# Solar_Battery_Charger.net
KiCad netlist of a schematic drawn in Altium Designer
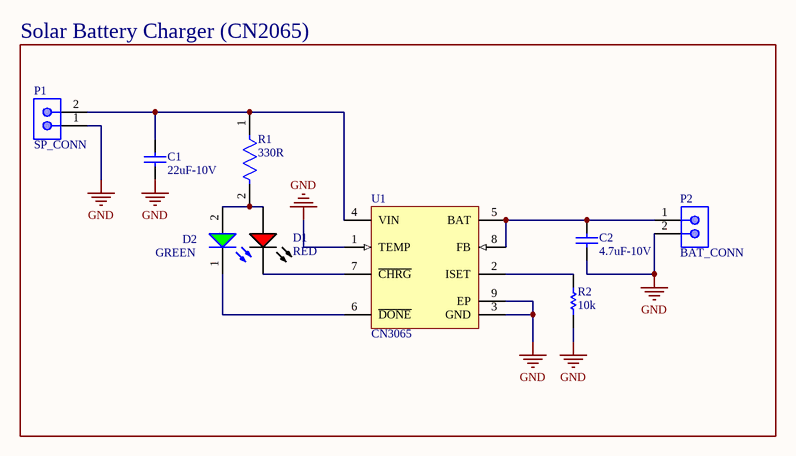
[diagram p0: Solar Battery Charger.SchDoc]

(export (version "E")
  (design (tool "Eeschema 10.0.6"))
  (components
    (comp (ref "C1")
      (value "22uF-10V")
      (footprint "CAPC2013X95X45ML15T25")
      (fields (field (name "MANUFACTURER") "Murata") (field (name "PART NUMBER") "GRM219R61A226MEA0D"))
      (libsource (lib "Altium Content Vault") (part "CAP"))
    )
    (comp (ref "C2")
      (value "4.7uF-10V")
      (footprint "CAPC2013X95X45LL10T25")
      (fields (field (name "MANUFACTURER") "Murata") (field (name "PART NUMBER") "GRM219R61A475KE34J"))
      (libsource (lib "Altium Content Vault") (part "CAP"))
    )
    (comp (ref "D1")
      (value "RED")
      (footprint "AVAG-HSMX-C190_V")
      (description "LED Uni-Color Red, 65 mW, 20 mA, -40 to 85 degC, 2-Pin SMD, RoHS, Tape and Reel")
      (libsource (lib "Altium Content Vault") (part "LED-RED-AK-2"))
    )
    (comp (ref "D2")
      (value "GREEN")
      (footprint "WL-SMCW_0603_150060xx75000")
      (description "WURTH ELEKTRONIK - 150060VS75000 - LED, Green, SMD, 0603, 30 mA, 2 V, 570 nm")
      (libsource (lib "Altium Content Vault") (part "LED_Green_2A-1K"))
    )
    (comp (ref "P1")
      (value "SP_CONN")
      (footprint "MOLX-22-23-2021_V")
      (fields (field (name "PARTNUMBER") "22-23-2021"))
      (libsource (lib "Altium Content Vault") (part "CN-1P-M-R2"))
    )
    (comp (ref "P2")
      (value "BAT_CONN")
      (footprint "MOLX-22-23-2021_V")
      (fields (field (name "PARTNUMBER") "22-23-2021"))
      (libsource (lib "") (part "CN-1P-M-R2_1"))
    )
    (comp (ref "R1")
      (value "330R")
      (footprint "FP-CRCW0603-e3-MFG")
      (description "RES Thick Film, 330Ω, 1%, 0.1W, 100ppm/°C, 0603")
      (fields (field (name "TOLERANCE") "1%"))
      (libsource (lib "Altium Content Vault") (part "1029c3af85768c4190bb7ad29bc67b5"))
    )
    (comp (ref "R2")
      (value "10k")
      (footprint "RESC2013X60X35NL10T20")
      (description "Chip Resistor, 10 KOhm, +/- 1%, 0.125 W, -55 to 155 degC, 0805 (2012 Metric), RoHS, Tape and Reel")
      (fields (field (name "MANUFACTURER") "Yageo"))
      (libsource (lib "Altium Content Vault") (part "RES-2"))
    )
    (comp (ref "U1")
      (value "CN3065")
      (footprint "CONS-DFN-8_M")
      (fields (field (name "MANUFACTURER") "Consonance Electronic"))
      (libsource (lib "Altium Content Vault") (part "CONS-CN3065-DFN-8"))
    )
  )
  (nets
    (net (code "1") (name "GND") (class "Default")
      (node (ref "C1") (pin "1") (pinfunction "1_1") (pintype "passive"))
      (node (ref "C2") (pin "2") (pinfunction "2_2") (pintype "passive"))
      (node (ref "P1") (pin "1") (pinfunction "1_1") (pintype "passive"))
      (node (ref "P2") (pin "2") (pinfunction "2_2") (pintype "passive"))
      (node (ref "R2") (pin "2") (pinfunction "2_2") (pintype "passive"))
      (node (ref "U1") (pin "1") (pinfunction "TEMP_1") (pintype "input"))
      (node (ref "U1") (pin "3") (pinfunction "GND_3") (pintype "power_in"))
      (node (ref "U1") (pin "9") (pinfunction "EP_9") (pintype "passive"))
    )
    (net (code "2") (name "Net-(D1-A)") (class "Default")
      (node (ref "D1") (pin "1") (pinfunction "A_1") (pintype "passive"))
      (node (ref "D2") (pin "2") (pinfunction "A_2") (pintype "passive"))
      (node (ref "R1") (pin "2") (pinfunction "2_2") (pintype "passive"))
    )
    (net (code "3") (name "Net-(D1-K)") (class "Default")
      (node (ref "D1") (pin "2") (pinfunction "K_2") (pintype "passive"))
      (node (ref "U1") (pin "7") (pinfunction "~{CHRG}_7") (pintype "tri_state"))
    )
    (net (code "4") (name "Net-(D2-K)") (class "Default")
      (node (ref "D2") (pin "1") (pinfunction "K_1") (pintype "passive"))
      (node (ref "U1") (pin "6") (pinfunction "~{DONE}_6") (pintype "tri_state"))
    )
    (net (code "5") (name "Net-(U1-BAT)") (class "Default")
      (node (ref "C2") (pin "1") (pinfunction "1_1") (pintype "passive"))
      (node (ref "P2") (pin "1") (pinfunction "1_1") (pintype "passive"))
      (node (ref "U1") (pin "5") (pinfunction "BAT_5") (pintype "power_in"))
      (node (ref "U1") (pin "8") (pinfunction "FB_8") (pintype "input"))
    )
    (net (code "6") (name "Net-(U1-ISET)") (class "Default")
      (node (ref "R2") (pin "1") (pinfunction "1_1") (pintype "passive"))
      (node (ref "U1") (pin "2") (pinfunction "ISET_2") (pintype "passive"))
    )
    (net (code "7") (name "Net-(U1-VIN)") (class "Default")
      (node (ref "C1") (pin "2") (pinfunction "2_2") (pintype "passive"))
      (node (ref "P1") (pin "2") (pinfunction "2_2") (pintype "passive"))
      (node (ref "R1") (pin "1") (pinfunction "1_1") (pintype "passive"))
      (node (ref "U1") (pin "4") (pinfunction "VIN_4") (pintype "power_in"))
    )
  )
)
